# DIOT_CONN.net
KiCad netlist of a schematic drawn in Altium Designer
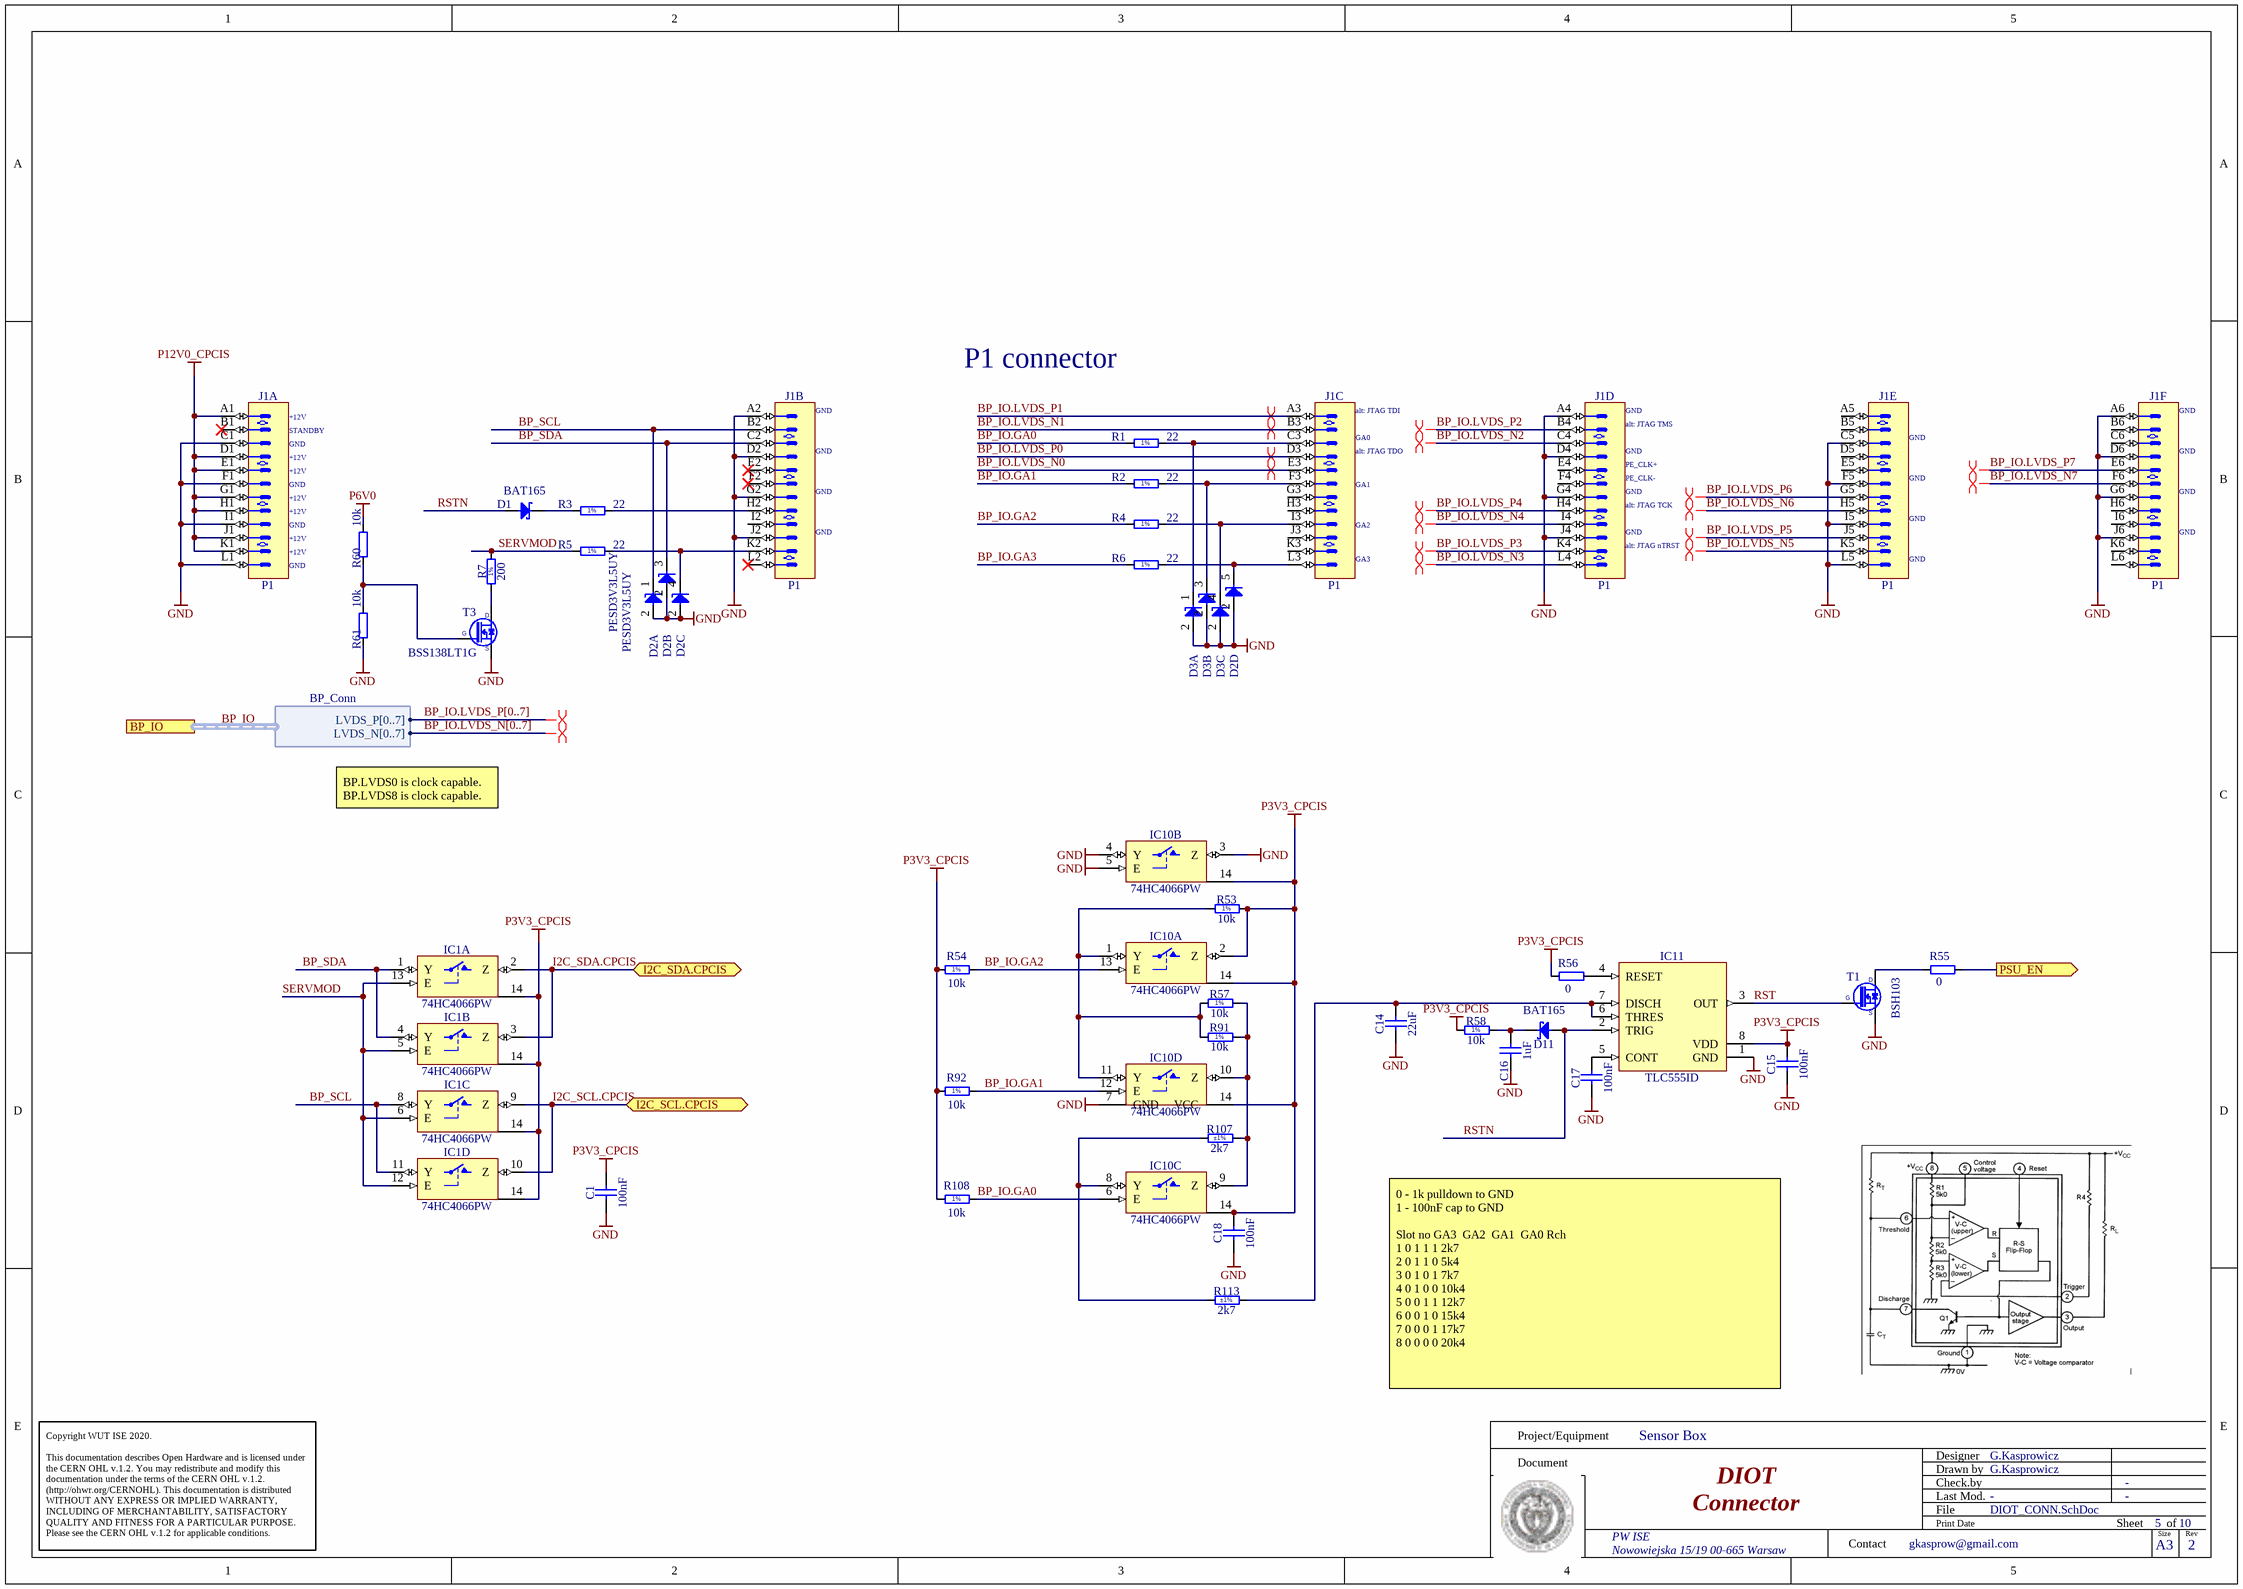
[diagram p0: DIOT_CONN.SchDoc]

(export (version "E")
  (design (tool "Eeschema 10.0.6"))
  (components
    (comp (ref "C1")
      (value "100nF")
      (footprint "CAPC1005X55N")
      (description "Non-polarised capacitor")
      (fields
        (field (name "PART NUMBER") "CC0402_100NF_16V_10%_X5R")
        (field (name "VOLTAGE") "16V")
        (field (name "AUTHOR") "CERN DEM JLC")
      )
      (libsource (lib "Capacitors") (part "Capacitor - non polarized"))
    )
    (comp (ref "C14")
      (value "22uF")
      (footprint "CAPC2012X135N")
      (description "Non-polarised capacitor")
      (fields
        (field (name "MANUFACTURER") "GENERIC")
        (field (name "PART NUMBER") "CC0805_22UF_16V_10%_X5R")
        (field (name "AUTHOR") "CERN DEM JLC")
      )
      (libsource (lib "Capacitors") (part "Capacitor - non polarized"))
    )
    (comp (ref "C15")
      (value "100nF")
      (footprint "CAPC1005X55N")
      (description "Non-polarised capacitor")
      (fields
        (field (name "PART NUMBER") "CC0402_100NF_16V_10%_X5R")
        (field (name "VOLTAGE") "16V")
        (field (name "AUTHOR") "CERN DEM JLC")
      )
      (libsource (lib "Capacitors") (part "Capacitor - non polarized"))
    )
    (comp (ref "C16")
      (value "1uF")
      (footprint "CAPC1608X87N")
      (description "Non-polarised capacitor")
      (fields
        (field (name "PART NUMBER") "CC0603_1UF_25V_10%_X7R")
        (field (name "VOLTAGE") "25V")
        (field (name "AUTHOR") "CERN DEM JLC")
      )
      (libsource (lib "Capacitors") (part "Capacitor - non polarized"))
    )
    (comp (ref "C17")
      (value "100nF")
      (footprint "CAPC1005X55N")
      (description "Non-polarised capacitor")
      (fields
        (field (name "PART NUMBER") "CC0402_100NF_16V_10%_X5R")
        (field (name "VOLTAGE") "16V")
        (field (name "AUTHOR") "CERN DEM JLC")
      )
      (libsource (lib "Capacitors") (part "Capacitor - non polarized"))
    )
    (comp (ref "C18")
      (value "100nF")
      (footprint "CAPC1005X55N")
      (description "Non-polarised capacitor")
      (fields
        (field (name "PART NUMBER") "CC0402_100NF_16V_10%_X5R")
        (field (name "VOLTAGE") "16V")
        (field (name "AUTHOR") "CERN DEM JLC")
      )
      (libsource (lib "Capacitors") (part "Capacitor - non polarized"))
    )
    (comp (ref "D1")
      (value "BAT165")
      (footprint "SOD2512X110N")
      (description "Schottky Diode")
      (fields
        (field (name "MANUFACTURER") "INFINEON")
        (field (name "VOLTAGE") "40V")
        (field (name "AUTHOR") "CERN DEM JLC")
      )
      (libsource (lib "ICs And Semiconductors") (part "Diode Schottky"))
    )
    (comp (ref "D2")
      (value "PESD3V3L5UY")
      (footprint "SOT65P210X110-6N")
      (description "Fivefold ESD Protection Diode Arrays")
      (fields
        (field (name "VOLTAGE") "3.3V")
        (field (name "POWER") "200W")
        (field (name "AUTHOR") "CERN DEM WB")
      )
      (libsource (lib "ICs And Semiconductors") (part "PESD Array 5diodes 6pins Common anode2"))
    )
    (comp (ref "D3")
      (value "PESD3V3L5UY")
      (footprint "SOT65P210X110-6N")
      (description "Fivefold ESD Protection Diode Arrays")
      (fields
        (field (name "VOLTAGE") "3.3V")
        (field (name "POWER") "200W")
        (field (name "AUTHOR") "CERN DEM WB")
      )
      (libsource (lib "ICs And Semiconductors") (part "PESD Array 5diodes 6pins Common anode2"))
    )
    (comp (ref "D11")
      (value "BAT165")
      (footprint "SOD2512X110N")
      (description "Schottky Diode")
      (fields
        (field (name "MANUFACTURER") "INFINEON")
        (field (name "VOLTAGE") "40V")
        (field (name "AUTHOR") "CERN DEM JLC")
      )
      (libsource (lib "ICs And Semiconductors") (part "Diode Schottky"))
    )
    (comp (ref "IC1")
      (value "74HC4066PW")
      (footprint "SOP65P640X110-14N")
      (fields (field (name "MANUFACTURER") "NXP SEMICONDUCTORS") (field (name "AUTHOR") "CERN DEM JLC"))
      (libsource (lib "ICs And Semiconductors") (part "4066"))
    )
    (comp (ref "IC10")
      (value "74HC4066PW")
      (footprint "SOP65P640X110-14N")
      (fields (field (name "MANUFACTURER") "NXP SEMICONDUCTORS") (field (name "AUTHOR") "CERN DEM JLC"))
      (libsource (lib "ICs And Semiconductors") (part "4066"))
    )
    (comp (ref "IC11")
      (value "TLC555ID")
      (footprint "SOIC127P600X175-8N")
      (description "LinCMOS Timer")
      (fields (field (name "MANUFACTURER") "TEXAS INSTRUMENTS") (field (name "AUTHOR") "CERN DEM JMW"))
      (libsource (lib "ICs And Semiconductors") (part "TLC555"))
    )
    (comp (ref "J1")
      (value "P1")
      (footprint "AMPHENOL_10052825-101LF")
      (description "72 Contacts Header, 6 Columns, 4 Pairs per Column")
      (fields
        (field (name "PART NUMBER") "AMPHENOL_10052825-101LF")
        (field (name "MANUFACTURER") "AMPHENOL")
        (field (name "AUTHOR") "CERN DEM MR")
      )
      (libsource (lib "Connectors") (part "AMPHENOL_10052825-101LF"))
    )
    (comp (ref "R1")
      (value "22")
      (footprint "RESC1005X40N")
      (description "Resistor - 1%")
      (fields
        (field (name "PART NUMBER") "R0402_22R_1%_0.0625W_100PPM")
        (field (name "POWER") "0.0625W")
        (field (name "AUTHOR") "CERN DEM JLC")
      )
      (libsource (lib "Resistors") (part "Resistor - 1%"))
    )
    (comp (ref "R2")
      (value "22")
      (footprint "RESC1005X40N")
      (description "Resistor - 1%")
      (fields
        (field (name "PART NUMBER") "R0402_22R_1%_0.0625W_100PPM")
        (field (name "POWER") "0.0625W")
        (field (name "AUTHOR") "CERN DEM JLC")
      )
      (libsource (lib "Resistors") (part "Resistor - 1%"))
    )
    (comp (ref "R3")
      (value "22")
      (footprint "RESC1005X40N")
      (description "Resistor - 1%")
      (fields
        (field (name "PART NUMBER") "R0402_22R_1%_0.0625W_100PPM")
        (field (name "POWER") "0.0625W")
        (field (name "AUTHOR") "CERN DEM JLC")
      )
      (libsource (lib "Resistors") (part "Resistor - 1%"))
    )
    (comp (ref "R4")
      (value "22")
      (footprint "RESC1005X40N")
      (description "Resistor - 1%")
      (fields
        (field (name "PART NUMBER") "R0402_22R_1%_0.0625W_100PPM")
        (field (name "POWER") "0.0625W")
        (field (name "AUTHOR") "CERN DEM JLC")
      )
      (libsource (lib "Resistors") (part "Resistor - 1%"))
    )
    (comp (ref "R5")
      (value "22")
      (footprint "RESC1005X40N")
      (description "Resistor - 1%")
      (fields
        (field (name "PART NUMBER") "R0402_22R_1%_0.0625W_100PPM")
        (field (name "POWER") "0.0625W")
        (field (name "AUTHOR") "CERN DEM JLC")
      )
      (libsource (lib "Resistors") (part "Resistor - 1%"))
    )
    (comp (ref "R6")
      (value "22")
      (footprint "RESC1005X40N")
      (description "Resistor - 1%")
      (fields
        (field (name "PART NUMBER") "R0402_22R_1%_0.0625W_100PPM")
        (field (name "POWER") "0.0625W")
        (field (name "AUTHOR") "CERN DEM JLC")
      )
      (libsource (lib "Resistors") (part "Resistor - 1%"))
    )
    (comp (ref "R7")
      (value "200")
      (footprint "RESC1005X40N")
      (description "Resistor - 1%")
      (fields
        (field (name "PART NUMBER") "R0402_200R_1%_0.0625W_100PPM")
        (field (name "POWER") "0.0625W")
        (field (name "AUTHOR") "CERN DEM JLC")
      )
      (libsource (lib "Resistors") (part "Resistor - 1%"))
    )
    (comp (ref "R53")
      (value "10k")
      (footprint "RESC1005X40N")
      (description "Resistor - 1%")
      (fields
        (field (name "PART NUMBER") "R0402_1K_1%_0.0625W_100PPM")
        (field (name "POWER") "0.0625W")
        (field (name "AUTHOR") "CERN DEM JLC")
      )
      (libsource (lib "Resistors") (part "Resistor - 1%"))
    )
    (comp (ref "R54")
      (value "10k")
      (footprint "RESC1005X40N")
      (description "Resistor - 1%")
      (fields
        (field (name "PART NUMBER") "R0402_10K_1%_0.0625W_100PPM")
        (field (name "POWER") "0.0625W")
        (field (name "AUTHOR") "CERN DEM JLC")
      )
      (libsource (lib "Resistors") (part "Resistor - 1%"))
    )
    (comp (ref "R55")
      (value "0")
      (footprint "RESC1005X40N")
      (description "Resistor")
      (fields
        (field (name "PART NUMBER") "R0402_0R_JUMPER")
        (field (name "MANUFACTURER") "GENERIC")
        (field (name "AUTHOR") "CERN DEM JLC")
      )
      (libsource (lib "Resistors") (part "Resistor"))
    )
    (comp (ref "R56")
      (value "0")
      (footprint "RESC1005X40N")
      (description "Resistor")
      (fields
        (field (name "PART NUMBER") "R0402_0R_JUMPER")
        (field (name "MANUFACTURER") "GENERIC")
        (field (name "AUTHOR") "CERN DEM JLC")
      )
      (libsource (lib "Resistors") (part "Resistor"))
    )
    (comp (ref "R57")
      (value "10k")
      (footprint "RESC1005X40N")
      (description "Resistor - 1%")
      (fields
        (field (name "PART NUMBER") "R0402_1K_1%_0.0625W_100PPM")
        (field (name "POWER") "0.0625W")
        (field (name "AUTHOR") "CERN DEM JLC")
      )
      (libsource (lib "Resistors") (part "Resistor - 1%"))
    )
    (comp (ref "R58")
      (value "10k")
      (footprint "RESC1005X40N")
      (description "Resistor - 1%")
      (fields
        (field (name "PART NUMBER") "R0402_10K_1%_0.0625W_100PPM")
        (field (name "POWER") "0.0625W")
        (field (name "AUTHOR") "CERN DEM JLC")
      )
      (libsource (lib "Resistors") (part "Resistor - 1%"))
    )
    (comp (ref "R60")
      (value "10k")
      (footprint "RESC1005X40N")
      (description "Resistor - 1%")
      (fields
        (field (name "PART NUMBER") "R0402_10K_1%_0.0625W_100PPM")
        (field (name "POWER") "0.0625W")
        (field (name "AUTHOR") "CERN DEM JLC")
      )
      (libsource (lib "Resistors") (part "Resistor - 1%"))
    )
    (comp (ref "R61")
      (value "10k")
      (footprint "RESC1005X40N")
      (description "Resistor - 1%")
      (fields
        (field (name "PART NUMBER") "R0402_10K_1%_0.0625W_100PPM")
        (field (name "POWER") "0.0625W")
        (field (name "AUTHOR") "CERN DEM JLC")
      )
      (libsource (lib "Resistors") (part "Resistor - 1%"))
    )
    (comp (ref "R91")
      (value "10k")
      (footprint "RESC1005X40N")
      (description "Resistor - 1%")
      (fields
        (field (name "PART NUMBER") "R0402_1K_1%_0.0625W_100PPM")
        (field (name "POWER") "0.0625W")
        (field (name "AUTHOR") "CERN DEM JLC")
      )
      (libsource (lib "Resistors") (part "Resistor - 1%"))
    )
    (comp (ref "R92")
      (value "10k")
      (footprint "RESC1005X40N")
      (description "Resistor - 1%")
      (fields
        (field (name "PART NUMBER") "R0402_10K_1%_0.0625W_100PPM")
        (field (name "POWER") "0.0625W")
        (field (name "AUTHOR") "CERN DEM JLC")
      )
      (libsource (lib "Resistors") (part "Resistor - 1%"))
    )
    (comp (ref "R107")
      (value "2k7")
      (footprint "RESC1608X55N")
      (description "Resistor - 1%")
      (fields
        (field (name "PART NUMBER") "R0603_2K7_1%_0.1W_100PPM")
        (field (name "POWER") "0.1W")
        (field (name "TOLERANCE") "±1%")
        (field (name "AUTHOR") "CERN DEM JLC")
      )
      (libsource (lib "") (part "Resistor - 1%_1"))
    )
    (comp (ref "R108")
      (value "10k")
      (footprint "RESC1005X40N")
      (description "Resistor - 1%")
      (fields
        (field (name "PART NUMBER") "R0402_10K_1%_0.0625W_100PPM")
        (field (name "POWER") "0.0625W")
        (field (name "AUTHOR") "CERN DEM JLC")
      )
      (libsource (lib "Resistors") (part "Resistor - 1%"))
    )
    (comp (ref "R113")
      (value "2k7")
      (footprint "RESC1608X55N")
      (description "Resistor - 1%")
      (fields
        (field (name "PART NUMBER") "R0603_2K7_1%_0.1W_100PPM")
        (field (name "POWER") "0.1W")
        (field (name "TOLERANCE") "±1%")
        (field (name "AUTHOR") "CERN DEM JLC")
      )
      (libsource (lib "") (part "Resistor - 1%_1"))
    )
    (comp (ref "T1")
      (value "BSH103")
      (footprint "SOT95P230X110-3N")
      (description "N-CHANNEL MOSFET WITH DIODE")
      (fields (field (name "MANUFACTURER") "NEXPERIA") (field (name "AUTHOR") "CERN DEM JLC"))
      (libsource (lib "ICs And Semiconductors") (part "N-MOSFET-D 1G 2S 3D"))
    )
    (comp (ref "T3")
      (value "BSS138LT1G")
      (footprint "SOT95P240X110-3N")
      (description "N-CHANNEL MOSFET WITH DIODE")
      (fields
        (field (name "MANUFACTURER") "ON SEMICONDUCTOR")
        (field (name "MANUFACTURER PART NUMBER") "BSS138L")
        (field (name "AUTHOR") "CERN DEM JLC")
      )
      (libsource (lib "ICs And Semiconductors") (part "N-MOSFET-D 1G 2S 3D"))
    )
  )
  (nets
    (net (code "2") (name "/BP_IO.GA0") (class "Default")
      (node (ref "IC10") (pin "6") (pinfunction "E_6") (pintype "input"))
      (node (ref "R1") (pin "1") (pinfunction "1_1") (pintype "passive"))
      (node (ref "R108") (pin "2") (pinfunction "2_2") (pintype "passive"))
    )
    (net (code "3") (name "/BP_IO.GA1") (class "Default")
      (node (ref "IC10") (pin "12") (pinfunction "E_12") (pintype "input"))
      (node (ref "R2") (pin "1") (pinfunction "1_1") (pintype "passive"))
      (node (ref "R92") (pin "2") (pinfunction "2_2") (pintype "passive"))
    )
    (net (code "4") (name "/BP_IO.GA2") (class "Default")
      (node (ref "IC10") (pin "13") (pinfunction "E_13") (pintype "input"))
      (node (ref "R4") (pin "1") (pinfunction "1_1") (pintype "passive"))
      (node (ref "R54") (pin "2") (pinfunction "2_2") (pintype "passive"))
    )
    (net (code "5") (name "/BP_IO.GA3") (class "Default")
      (node (ref "R6") (pin "1") (pinfunction "1_1") (pintype "passive"))
    )
    (net (code "6") (name "/BP_IO.LVDS_N0") (class "Default")
      (node (ref "J1") (pin "E3") (pinfunction "E3_E3") (pintype "bidirectional"))
    )
    (net (code "7") (name "/BP_IO.LVDS_N1") (class "Default")
      (node (ref "J1") (pin "B3") (pinfunction "B3_B3") (pintype "bidirectional"))
    )
    (net (code "8") (name "/BP_IO.LVDS_N2") (class "Default")
      (node (ref "J1") (pin "C4") (pinfunction "C4_C4") (pintype "bidirectional"))
    )
    (net (code "9") (name "/BP_IO.LVDS_N3") (class "Default")
      (node (ref "J1") (pin "L4") (pinfunction "L4_L4") (pintype "bidirectional"))
    )
    (net (code "10") (name "/BP_IO.LVDS_N4") (class "Default")
      (node (ref "J1") (pin "I4") (pinfunction "I4_I4") (pintype "bidirectional"))
    )
    (net (code "11") (name "/BP_IO.LVDS_N5") (class "Default")
      (node (ref "J1") (pin "K5") (pinfunction "K5_K5") (pintype "bidirectional"))
    )
    (net (code "12") (name "/BP_IO.LVDS_N6") (class "Default")
      (node (ref "J1") (pin "H5") (pinfunction "H5_H5") (pintype "bidirectional"))
    )
    (net (code "13") (name "/BP_IO.LVDS_N7") (class "Default")
      (node (ref "J1") (pin "F6") (pinfunction "F6_F6") (pintype "bidirectional"))
    )
    (net (code "15") (name "/BP_IO.LVDS_P0") (class "Default")
      (node (ref "J1") (pin "D3") (pinfunction "D3_D3") (pintype "bidirectional"))
    )
    (net (code "16") (name "/BP_IO.LVDS_P1") (class "Default")
      (node (ref "J1") (pin "A3") (pinfunction "A3_A3") (pintype "bidirectional"))
    )
    (net (code "17") (name "/BP_IO.LVDS_P2") (class "Default")
      (node (ref "J1") (pin "B4") (pinfunction "B4_B4") (pintype "bidirectional"))
    )
    (net (code "18") (name "/BP_IO.LVDS_P3") (class "Default")
      (node (ref "J1") (pin "K4") (pinfunction "K4_K4") (pintype "bidirectional"))
    )
    (net (code "19") (name "/BP_IO.LVDS_P4") (class "Default")
      (node (ref "J1") (pin "H4") (pinfunction "H4_H4") (pintype "bidirectional"))
    )
    (net (code "20") (name "/BP_IO.LVDS_P5") (class "Default")
      (node (ref "J1") (pin "J5") (pinfunction "J5_J5") (pintype "bidirectional"))
    )
    (net (code "21") (name "/BP_IO.LVDS_P6") (class "Default")
      (node (ref "J1") (pin "G5") (pinfunction "G5_G5") (pintype "bidirectional"))
    )
    (net (code "22") (name "/BP_IO.LVDS_P7") (class "Default")
      (node (ref "J1") (pin "E6") (pinfunction "E6_E6") (pintype "bidirectional"))
    )
    (net (code "23") (name "/BP_SCL") (class "Default")
      (node (ref "D2") (pin "1") (pinfunction "C_1") (pintype "passive"))
      (node (ref "IC1") (pin "11") (pinfunction "Y_11") (pintype "bidirectional"))
      (node (ref "IC1") (pin "8") (pinfunction "Y_8") (pintype "bidirectional"))
      (node (ref "J1") (pin "B2") (pinfunction "B2_B2") (pintype "bidirectional"))
    )
    (net (code "24") (name "/BP_SDA") (class "Default")
      (node (ref "D2") (pin "3") (pinfunction "C_3") (pintype "passive"))
      (node (ref "IC1") (pin "1") (pinfunction "Y_1") (pintype "bidirectional"))
      (node (ref "IC1") (pin "4") (pinfunction "Y_4") (pintype "bidirectional"))
      (node (ref "J1") (pin "C2") (pinfunction "C2_C2") (pintype "bidirectional"))
    )
    (net (code "25") (name "/I2C_SCL.CPCIS") (class "Default")
      (node (ref "IC1") (pin "10") (pinfunction "Z_10") (pintype "bidirectional"))
      (node (ref "IC1") (pin "9") (pinfunction "Z_9") (pintype "bidirectional"))
    )
    (net (code "26") (name "/I2C_SDA.CPCIS") (class "Default")
      (node (ref "IC1") (pin "2") (pinfunction "Z_2") (pintype "bidirectional"))
      (node (ref "IC1") (pin "3") (pinfunction "Z_3") (pintype "bidirectional"))
    )
    (net (code "27") (name "/PSU_EN") (class "Default")
      (node (ref "R55") (pin "1") (pinfunction "1_1") (pintype "passive"))
    )
    (net (code "28") (name "/RST") (class "Default")
      (node (ref "IC11") (pin "3") (pinfunction "OUT_3") (pintype "output"))
      (node (ref "T1") (pin "1") (pinfunction "G_1") (pintype "passive"))
    )
    (net (code "29") (name "/RSTN") (class "Default")
      (node (ref "D1") (pin "2") (pinfunction "A_2") (pintype "passive"))
      (node (ref "D11") (pin "2") (pinfunction "A_2") (pintype "passive"))
      (node (ref "IC11") (pin "2") (pinfunction "TRIG_2") (pintype "input"))
    )
    (net (code "30") (name "/SERVMOD") (class "Default")
      (node (ref "IC1") (pin "12") (pinfunction "E_12") (pintype "input"))
      (node (ref "IC1") (pin "13") (pinfunction "E_13") (pintype "input"))
      (node (ref "IC1") (pin "5") (pinfunction "E_5") (pintype "input"))
      (node (ref "IC1") (pin "6") (pinfunction "E_6") (pintype "input"))
      (node (ref "R5") (pin "1") (pinfunction "1_1") (pintype "passive"))
      (node (ref "R7") (pin "2") (pinfunction "2_2") (pintype "passive"))
    )
    (net (code "33") (name "GND") (class "Default")
      (node (ref "C1") (pin "1") (pinfunction "1_1") (pintype "passive"))
      (node (ref "C14") (pin "1") (pinfunction "1_1") (pintype "passive"))
      (node (ref "C15") (pin "1") (pinfunction "1_1") (pintype "passive"))
      (node (ref "C16") (pin "1") (pinfunction "1_1") (pintype "passive"))
      (node (ref "C17") (pin "1") (pinfunction "1_1") (pintype "passive"))
      (node (ref "C18") (pin "1") (pinfunction "1_1") (pintype "passive"))
      (node (ref "D2") (pin "2") (pinfunction "A_2") (pintype "passive"))
      (node (ref "D3") (pin "2") (pinfunction "A_2") (pintype "passive"))
      (node (ref "IC1") (pin "7") (pinfunction "GND_7") (pintype "power_in"))
      (node (ref "IC10") (pin "3") (pinfunction "Z_3") (pintype "bidirectional"))
      (node (ref "IC10") (pin "4") (pinfunction "Y_4") (pintype "bidirectional"))
      (node (ref "IC10") (pin "5") (pinfunction "E_5") (pintype "input"))
      (node (ref "IC10") (pin "7") (pinfunction "GND_7") (pintype "power_in"))
      (node (ref "IC11") (pin "1") (pinfunction "GND_1") (pintype "power_in"))
      (node (ref "J1") (pin "A2") (pinfunction "A2_A2") (pintype "bidirectional"))
      (node (ref "J1") (pin "A4") (pinfunction "A4_A4") (pintype "bidirectional"))
      (node (ref "J1") (pin "A6") (pinfunction "A6_A6") (pintype "bidirectional"))
      (node (ref "J1") (pin "C1") (pinfunction "C1_C1") (pintype "bidirectional"))
      (node (ref "J1") (pin "C5") (pinfunction "C5_C5") (pintype "bidirectional"))
      (node (ref "J1") (pin "D2") (pinfunction "D2_D2") (pintype "bidirectional"))
      (node (ref "J1") (pin "D4") (pinfunction "D4_D4") (pintype "bidirectional"))
      (node (ref "J1") (pin "D6") (pinfunction "D6_D6") (pintype "bidirectional"))
      (node (ref "J1") (pin "F1") (pinfunction "F1_F1") (pintype "bidirectional"))
      (node (ref "J1") (pin "F5") (pinfunction "F5_F5") (pintype "bidirectional"))
      (node (ref "J1") (pin "G2") (pinfunction "G2_G2") (pintype "bidirectional"))
      (node (ref "J1") (pin "G4") (pinfunction "G4_G4") (pintype "bidirectional"))
      (node (ref "J1") (pin "G6") (pinfunction "G6_G6") (pintype "bidirectional"))
      (node (ref "J1") (pin "I1") (pinfunction "I1_I1") (pintype "bidirectional"))
      (node (ref "J1") (pin "I5") (pinfunction "I5_I5") (pintype "bidirectional"))
      (node (ref "J1") (pin "J2") (pinfunction "J2_J2") (pintype "bidirectional"))
      (node (ref "J1") (pin "J4") (pinfunction "J4_J4") (pintype "bidirectional"))
      (node (ref "J1") (pin "J6") (pinfunction "J6_J6") (pintype "bidirectional"))
      (node (ref "J1") (pin "L1") (pinfunction "L1_L1") (pintype "bidirectional"))
      (node (ref "J1") (pin "L5") (pinfunction "L5_L5") (pintype "bidirectional"))
      (node (ref "R61") (pin "2") (pinfunction "2_2") (pintype "passive"))
      (node (ref "T1") (pin "2") (pinfunction "S_2") (pintype "passive"))
      (node (ref "T3") (pin "2") (pinfunction "S_2") (pintype "passive"))
    )
    (net (code "34") (name "Net-(D1-C)") (class "Default")
      (node (ref "D1") (pin "1") (pinfunction "C_1") (pintype "passive"))
      (node (ref "R3") (pin "1") (pinfunction "1_1") (pintype "passive"))
    )
    (net (code "35") (name "Net-(D2C-C)") (class "Default")
      (node (ref "D2") (pin "4") (pinfunction "C_4") (pintype "passive"))
      (node (ref "J1") (pin "K2") (pinfunction "K2_K2") (pintype "bidirectional"))
      (node (ref "R5") (pin "2") (pinfunction "2_2") (pintype "passive"))
    )
    (net (code "36") (name "Net-(D2D-C)") (class "Default")
      (node (ref "D2") (pin "5") (pinfunction "C_5") (pintype "passive"))
      (node (ref "J1") (pin "L3") (pinfunction "L3_L3") (pintype "bidirectional"))
      (node (ref "R6") (pin "2") (pinfunction "2_2") (pintype "passive"))
    )
    (net (code "37") (name "Net-(D3A-C)") (class "Default")
      (node (ref "D3") (pin "1") (pinfunction "C_1") (pintype "passive"))
      (node (ref "J1") (pin "C3") (pinfunction "C3_C3") (pintype "bidirectional"))
      (node (ref "R1") (pin "2") (pinfunction "2_2") (pintype "passive"))
    )
    (net (code "38") (name "Net-(D3B-C)") (class "Default")
      (node (ref "D3") (pin "3") (pinfunction "C_3") (pintype "passive"))
      (node (ref "J1") (pin "F3") (pinfunction "F3_F3") (pintype "bidirectional"))
      (node (ref "R2") (pin "2") (pinfunction "2_2") (pintype "passive"))
    )
    (net (code "39") (name "Net-(D3C-C)") (class "Default")
      (node (ref "D3") (pin "4") (pinfunction "C_4") (pintype "passive"))
      (node (ref "J1") (pin "I3") (pinfunction "I3_I3") (pintype "bidirectional"))
      (node (ref "R4") (pin "2") (pinfunction "2_2") (pintype "passive"))
    )
    (net (code "40") (name "Net-(D11-C)") (class "Default")
      (node (ref "C16") (pin "2") (pinfunction "2_2") (pintype "passive"))
      (node (ref "D11") (pin "1") (pinfunction "C_1") (pintype "passive"))
      (node (ref "R58") (pin "2") (pinfunction "2_2") (pintype "passive"))
    )
    (net (code "41") (name "Net-(IC10A-Y)") (class "Default")
      (node (ref "IC10") (pin "1") (pinfunction "Y_1") (pintype "bidirectional"))
      (node (ref "IC10") (pin "11") (pinfunction "Y_11") (pintype "bidirectional"))
      (node (ref "R53") (pin "1") (pinfunction "1_1") (pintype "passive"))
      (node (ref "R57") (pin "1") (pinfunction "1_1") (pintype "passive"))
      (node (ref "R91") (pin "1") (pinfunction "1_1") (pintype "passive"))
    )
    (net (code "42") (name "Net-(IC10C-Y)") (class "Default")
      (node (ref "IC10") (pin "8") (pinfunction "Y_8") (pintype "bidirectional"))
      (node (ref "R107") (pin "1") (pinfunction "1_1") (pintype "passive"))
      (node (ref "R113") (pin "1") (pinfunction "1_1") (pintype "passive"))
    )
    (net (code "43") (name "Net-(IC10C-Z)") (class "Default")
      (node (ref "IC10") (pin "10") (pinfunction "Z_10") (pintype "bidirectional"))
      (node (ref "IC10") (pin "9") (pinfunction "Z_9") (pintype "bidirectional"))
      (node (ref "R107") (pin "2") (pinfunction "2_2") (pintype "passive"))
      (node (ref "R57") (pin "2") (pinfunction "2_2") (pintype "passive"))
      (node (ref "R91") (pin "2") (pinfunction "2_2") (pintype "passive"))
    )
    (net (code "44") (name "Net-(IC11-CONT)") (class "Default")
      (node (ref "C17") (pin "2") (pinfunction "2_2") (pintype "passive"))
      (node (ref "IC11") (pin "5") (pinfunction "CONT_5") (pintype "input"))
    )
    (net (code "45") (name "Net-(IC11-DISCH)") (class "Default")
      (node (ref "C14") (pin "2") (pinfunction "2_2") (pintype "passive"))
      (node (ref "IC11") (pin "6") (pinfunction "THRES_6") (pintype "input"))
      (node (ref "IC11") (pin "7") (pinfunction "DISCH_7") (pintype "input"))
      (node (ref "R113") (pin "2") (pinfunction "2_2") (pintype "passive"))
    )
    (net (code "46") (name "Net-(IC11-RESET)") (class "Default")
      (node (ref "IC11") (pin "4") (pinfunction "RESET_4") (pintype "input"))
      (node (ref "R56") (pin "1") (pinfunction "1_1") (pintype "passive"))
    )
    (net (code "47") (name "Net-(J1-PadH2)") (class "Default")
      (node (ref "J1") (pin "H2") (pinfunction "H2_H2") (pintype "bidirectional"))
      (node (ref "R3") (pin "2") (pinfunction "2_2") (pintype "passive"))
    )
    (net (code "48") (name "Net-(T1-D)") (class "Default")
      (node (ref "R55") (pin "2") (pinfunction "2_2") (pintype "passive"))
      (node (ref "T1") (pin "3") (pinfunction "D_3") (pintype "passive"))
    )
    (net (code "49") (name "Net-(T3-D)") (class "Default")
      (node (ref "R7") (pin "1") (pinfunction "1_1") (pintype "passive"))
      (node (ref "T3") (pin "3") (pinfunction "D_3") (pintype "passive"))
    )
    (net (code "50") (name "Net-(T3-G)") (class "Default")
      (node (ref "R60") (pin "2") (pinfunction "2_2") (pintype "passive"))
      (node (ref "R61") (pin "1") (pinfunction "1_1") (pintype "passive"))
      (node (ref "T3") (pin "1") (pinfunction "G_1") (pintype "passive"))
    )
    (net (code "51") (name "P3V3_CPCIS") (class "Default")
      (node (ref "C1") (pin "2") (pinfunction "2_2") (pintype "passive"))
      (node (ref "C15") (pin "2") (pinfunction "2_2") (pintype "passive"))
      (node (ref "C18") (pin "2") (pinfunction "2_2") (pintype "passive"))
      (node (ref "IC1") (pin "14") (pinfunction "VCC_14") (pintype "power_in"))
      (node (ref "IC10") (pin "14") (pinfunction "VCC_14") (pintype "power_in"))
      (node (ref "IC10") (pin "2") (pinfunction "Z_2") (pintype "bidirectional"))
      (node (ref "IC11") (pin "8") (pinfunction "VDD_8") (pintype "power_in"))
      (node (ref "R108") (pin "1") (pinfunction "1_1") (pintype "passive"))
      (node (ref "R53") (pin "2") (pinfunction "2_2") (pintype "passive"))
      (node (ref "R54") (pin "1") (pinfunction "1_1") (pintype "passive"))
      (node (ref "R56") (pin "2") (pinfunction "2_2") (pintype "passive"))
      (node (ref "R58") (pin "1") (pinfunction "1_1") (pintype "passive"))
      (node (ref "R92") (pin "1") (pinfunction "1_1") (pintype "passive"))
    )
    (net (code "52") (name "P6V0") (class "Default")
      (node (ref "R60") (pin "1") (pinfunction "1_1") (pintype "passive"))
    )
    (net (code "53") (name "P12V0_CPCIS") (class "Default")
      (node (ref "J1") (pin "A1") (pinfunction "A1_A1") (pintype "bidirectional"))
      (node (ref "J1") (pin "D1") (pinfunction "D1_D1") (pintype "bidirectional"))
      (node (ref "J1") (pin "E1") (pinfunction "E1_E1") (pintype "bidirectional"))
      (node (ref "J1") (pin "G1") (pinfunction "G1_G1") (pintype "bidirectional"))
      (node (ref "J1") (pin "H1") (pinfunction "H1_H1") (pintype "bidirectional"))
      (node (ref "J1") (pin "J1") (pinfunction "J1_J1") (pintype "bidirectional"))
      (node (ref "J1") (pin "K1") (pinfunction "K1_K1") (pintype "bidirectional"))
    )
    (net (code "54") (name "unconnected-(J1-PadA5)") (class "Default")
      (node (ref "J1") (pin "A5") (pinfunction "A5_A5") (pintype "bidirectional"))
    )
    (net (code "55") (name "unconnected-(J1-PadB1)") (class "Default")
      (node (ref "J1") (pin "B1") (pinfunction "B1_B1") (pintype "bidirectional+no_connect"))
    )
    (net (code "56") (name "unconnected-(J1-PadB5)") (class "Default")
      (node (ref "J1") (pin "B5") (pinfunction "B5_B5") (pintype "bidirectional"))
    )
    (net (code "57") (name "unconnected-(J1-PadB6)") (class "Default")
      (node (ref "J1") (pin "B6") (pinfunction "B6_B6") (pintype "bidirectional"))
    )
    (net (code "58") (name "unconnected-(J1-PadC6)") (class "Default")
      (node (ref "J1") (pin "C6") (pinfunction "C6_C6") (pintype "bidirectional"))
    )
    (net (code "59") (name "unconnected-(J1-PadD5)") (class "Default")
      (node (ref "J1") (pin "D5") (pinfunction "D5_D5") (pintype "bidirectional"))
    )
    (net (code "60") (name "unconnected-(J1-PadE2)") (class "Default")
      (node (ref "J1") (pin "E2") (pinfunction "E2_E2") (pintype "bidirectional+no_connect"))
    )
    (net (code "61") (name "unconnected-(J1-PadE4)") (class "Default")
      (node (ref "J1") (pin "E4") (pinfunction "E4_E4") (pintype "bidirectional"))
    )
    (net (code "62") (name "unconnected-(J1-PadE5)") (class "Default")
      (node (ref "J1") (pin "E5") (pinfunction "E5_E5") (pintype "bidirectional"))
    )
    (net (code "63") (name "unconnected-(J1-PadF2)") (class "Default")
      (node (ref "J1") (pin "F2") (pinfunction "F2_F2") (pintype "bidirectional+no_connect"))
    )
    (net (code "64") (name "unconnected-(J1-PadF4)") (class "Default")
      (node (ref "J1") (pin "F4") (pinfunction "F4_F4") (pintype "bidirectional"))
    )
    (net (code "65") (name "unconnected-(J1-PadG3)") (class "Default")
      (node (ref "J1") (pin "G3") (pinfunction "G3_G3") (pintype "bidirectional"))
    )
    (net (code "66") (name "unconnected-(J1-PadH3)") (class "Default")
      (node (ref "J1") (pin "H3") (pinfunction "H3_H3") (pintype "bidirectional"))
    )
    (net (code "67") (name "unconnected-(J1-PadH6)") (class "Default")
      (node (ref "J1") (pin "H6") (pinfunction "H6_H6") (pintype "bidirectional"))
    )
    (net (code "68") (name "unconnected-(J1-PadI2)") (class "Default")
      (node (ref "J1") (pin "I2") (pinfunction "I2_I2") (pintype "bidirectional"))
    )
    (net (code "69") (name "unconnected-(J1-PadI6)") (class "Default")
      (node (ref "J1") (pin "I6") (pinfunction "I6_I6") (pintype "bidirectional"))
    )
    (net (code "70") (name "unconnected-(J1-PadJ3)") (class "Default")
      (node (ref "J1") (pin "J3") (pinfunction "J3_J3") (pintype "bidirectional"))
    )
    (net (code "71") (name "unconnected-(J1-PadK3)") (class "Default")
      (node (ref "J1") (pin "K3") (pinfunction "K3_K3") (pintype "bidirectional"))
    )
    (net (code "72") (name "unconnected-(J1-PadK6)") (class "Default")
      (node (ref "J1") (pin "K6") (pinfunction "K6_K6") (pintype "bidirectional"))
    )
    (net (code "73") (name "unconnected-(J1-PadL2)") (class "Default")
      (node (ref "J1") (pin "L2") (pinfunction "L2_L2") (pintype "bidirectional+no_connect"))
    )
    (net (code "74") (name "unconnected-(J1-PadL6)") (class "Default")
      (node (ref "J1") (pin "L6") (pinfunction "L6_L6") (pintype "bidirectional"))
    )
  )
)
